# controller.net
KiCad netlist of a schematic drawn in Altium Designer
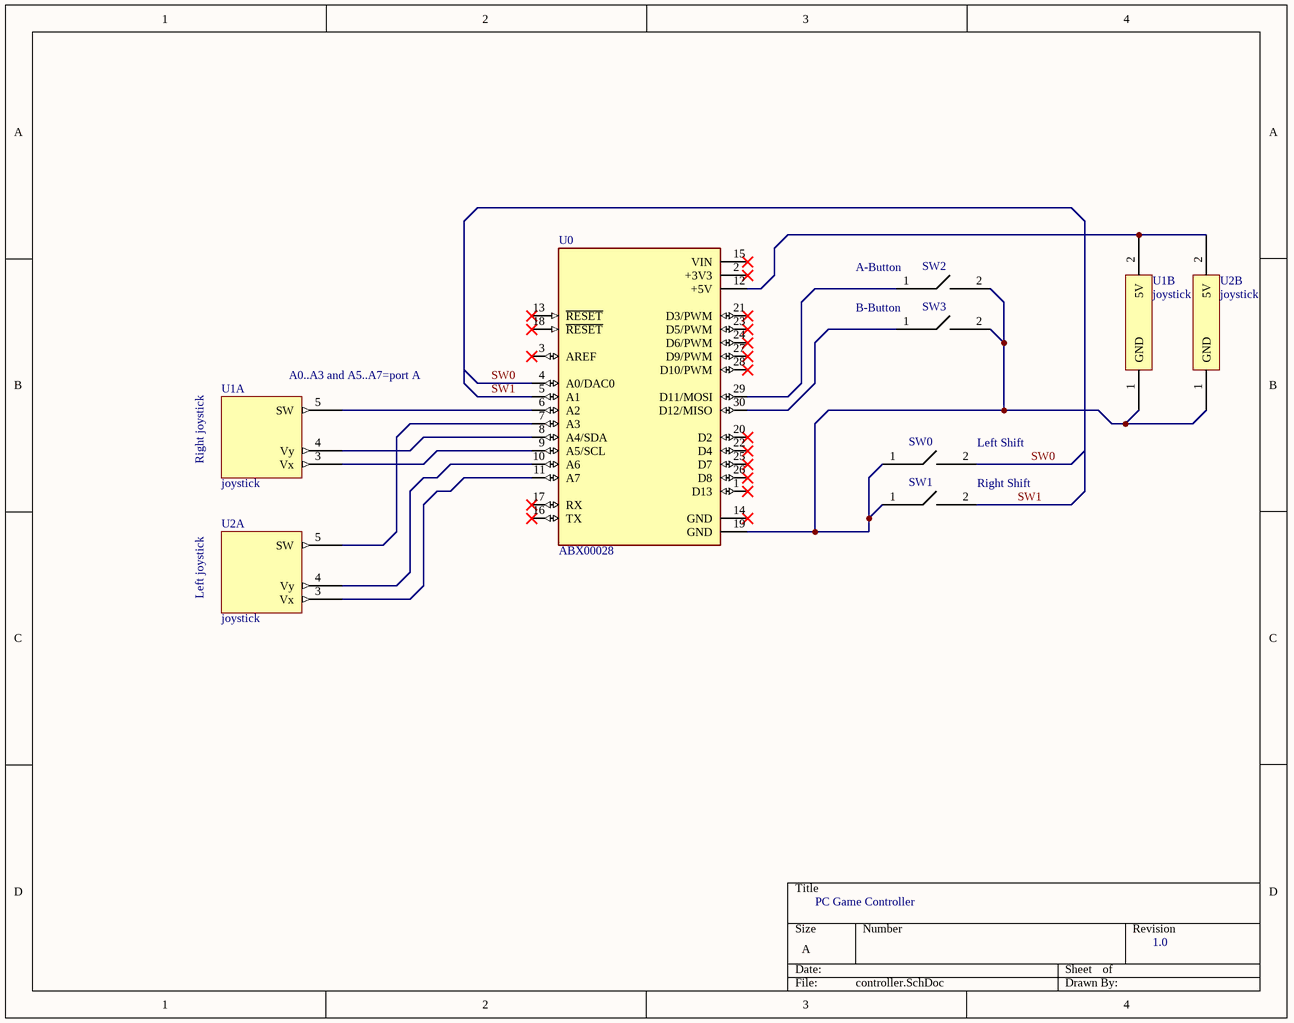
[diagram p0: controller.SchDoc]

(export (version "E")
  (design (tool "Eeschema 10.0.6"))
  (components
    (comp (ref "SW0") (value "~") (footprint "temp switch") (libsource (lib "button") (part "button")))
    (comp (ref "SW1") (value "~") (footprint "temp switch") (libsource (lib "button") (part "button")))
    (comp (ref "SW2") (value "~") (footprint "temp switch") (libsource (lib "button") (part "button")))
    (comp (ref "SW3") (value "~") (footprint "temp switch") (libsource (lib "button") (part "button")))
    (comp (ref "U0")
      (value "ABX00028")
      (footprint "MODULE_ABX00028")
      (description "Arduinoâ€™s 5V compatible board in the smallest available form factor: 45x18mm!")
      (fields (field (name "MP") "Arduino Nano Every") (field (name "MF") "Arduino"))
      (libsource (lib "ABX00028") (part "ABX00028"))
    )
    (comp (ref "U1") (value "joystick") (footprint "joystick") (libsource (lib "") (part "joystick_1")))
    (comp (ref "U2") (value "joystick") (footprint "joystick") (libsource (lib "") (part "joystick_1")))
  )
  (nets
    (net (code "1") (name "/SW0") (class "Default")
      (node (ref "SW0") (pin "2") (pintype "passive"))
      (node (ref "U0") (pin "4") (pinfunction "A0/DAC0_4") (pintype "bidirectional"))
    )
    (net (code "2") (name "/SW1") (class "Default")
      (node (ref "SW1") (pin "2") (pintype "passive"))
      (node (ref "U0") (pin "5") (pinfunction "A1_5") (pintype "bidirectional"))
    )
    (net (code "3") (name "Net-(U0-+5V)") (class "Default")
      (node (ref "U0") (pin "12") (pinfunction "+5V_12") (pintype "power_in"))
      (node (ref "U1") (pin "2") (pinfunction "5V_2") (pintype "power_in"))
      (node (ref "U2") (pin "2") (pinfunction "5V_2") (pintype "power_in"))
    )
    (net (code "4") (name "Net-(U0-A2)") (class "Default")
      (node (ref "U0") (pin "6") (pinfunction "A2_6") (pintype "bidirectional"))
      (node (ref "U1") (pin "5") (pinfunction "SW_5") (pintype "output"))
    )
    (net (code "5") (name "Net-(U0-A3)") (class "Default")
      (node (ref "U0") (pin "7") (pinfunction "A3_7") (pintype "bidirectional"))
      (node (ref "U2") (pin "5") (pinfunction "SW_5") (pintype "output"))
    )
    (net (code "6") (name "Net-(U0-A4{slash}SDA)") (class "Default")
      (node (ref "U0") (pin "8") (pinfunction "A4/SDA_8") (pintype "bidirectional"))
      (node (ref "U1") (pin "4") (pinfunction "Vy_4") (pintype "output"))
    )
    (net (code "7") (name "Net-(U0-A5{slash}SCL)") (class "Default")
      (node (ref "U0") (pin "9") (pinfunction "A5/SCL_9") (pintype "bidirectional"))
      (node (ref "U1") (pin "3") (pinfunction "Vx_3") (pintype "output"))
    )
    (net (code "8") (name "Net-(U0-A6)") (class "Default")
      (node (ref "U0") (pin "10") (pinfunction "A6_10") (pintype "bidirectional"))
      (node (ref "U2") (pin "4") (pinfunction "Vy_4") (pintype "output"))
    )
    (net (code "9") (name "Net-(U0-A7)") (class "Default")
      (node (ref "U0") (pin "11") (pinfunction "A7_11") (pintype "bidirectional"))
      (node (ref "U2") (pin "3") (pinfunction "Vx_3") (pintype "output"))
    )
    (net (code "10") (name "Net-(U0-D11{slash}MOSI)") (class "Default")
      (node (ref "SW2") (pin "1") (pintype "passive"))
      (node (ref "U0") (pin "29") (pinfunction "D11/MOSI_29") (pintype "bidirectional"))
    )
    (net (code "11") (name "Net-(U0-D12{slash}MISO)") (class "Default")
      (node (ref "SW3") (pin "1") (pintype "passive"))
      (node (ref "U0") (pin "30") (pinfunction "D12/MISO_30") (pintype "bidirectional"))
    )
    (net (code "12") (name "Net-(U1B-GND)") (class "Default")
      (node (ref "SW0") (pin "1") (pintype "passive"))
      (node (ref "SW1") (pin "1") (pintype "passive"))
      (node (ref "SW2") (pin "2") (pintype "passive"))
      (node (ref "SW3") (pin "2") (pintype "passive"))
      (node (ref "U0") (pin "19") (pinfunction "GND_19") (pintype "power_in"))
      (node (ref "U1") (pin "1") (pinfunction "GND_1") (pintype "power_in"))
      (node (ref "U2") (pin "1") (pinfunction "GND_1") (pintype "power_in"))
    )
    (net (code "13") (name "unconnected-(U0-+3V3-Pad2)") (class "Default")
      (node (ref "U0") (pin "2") (pinfunction "+3V3_2") (pintype "power_in+no_connect"))
    )
    (net (code "14") (name "unconnected-(U0-AREF-Pad3)") (class "Default")
      (node (ref "U0") (pin "3") (pinfunction "AREF_3") (pintype "bidirectional+no_connect"))
    )
    (net (code "15") (name "unconnected-(U0-D2-Pad20)") (class "Default")
      (node (ref "U0") (pin "20") (pinfunction "D2_20") (pintype "bidirectional+no_connect"))
    )
    (net (code "16") (name "unconnected-(U0-D3{slash}PWM-Pad21)") (class "Default")
      (node (ref "U0") (pin "21") (pinfunction "D3/PWM_21") (pintype "bidirectional+no_connect"))
    )
    (net (code "17") (name "unconnected-(U0-D4-Pad22)") (class "Default")
      (node (ref "U0") (pin "22") (pinfunction "D4_22") (pintype "bidirectional+no_connect"))
    )
    (net (code "18") (name "unconnected-(U0-D5{slash}PWM-Pad23)") (class "Default")
      (node (ref "U0") (pin "23") (pinfunction "D5/PWM_23") (pintype "bidirectional+no_connect"))
    )
    (net (code "19") (name "unconnected-(U0-D6{slash}PWM-Pad24)") (class "Default")
      (node (ref "U0") (pin "24") (pinfunction "D6/PWM_24") (pintype "bidirectional+no_connect"))
    )
    (net (code "20") (name "unconnected-(U0-D7-Pad25)") (class "Default")
      (node (ref "U0") (pin "25") (pinfunction "D7_25") (pintype "bidirectional+no_connect"))
    )
    (net (code "21") (name "unconnected-(U0-D8-Pad26)") (class "Default")
      (node (ref "U0") (pin "26") (pinfunction "D8_26") (pintype "bidirectional+no_connect"))
    )
    (net (code "22") (name "unconnected-(U0-D9{slash}PWM-Pad27)") (class "Default")
      (node (ref "U0") (pin "27") (pinfunction "D9/PWM_27") (pintype "bidirectional+no_connect"))
    )
    (net (code "23") (name "unconnected-(U0-D10{slash}PWM-Pad28)") (class "Default")
      (node (ref "U0") (pin "28") (pinfunction "D10/PWM_28") (pintype "bidirectional+no_connect"))
    )
    (net (code "24") (name "unconnected-(U0-D13-Pad1)") (class "Default")
      (node (ref "U0") (pin "1") (pinfunction "D13_1") (pintype "bidirectional+no_connect"))
    )
    (net (code "25") (name "unconnected-(U0-GND-Pad14)") (class "Default")
      (node (ref "U0") (pin "14") (pinfunction "GND_14") (pintype "power_in+no_connect"))
    )
    (net (code "26") (name "unconnected-(U0-RX-Pad17)") (class "Default")
      (node (ref "U0") (pin "17") (pinfunction "RX_17") (pintype "bidirectional+no_connect"))
    )
    (net (code "27") (name "unconnected-(U0-TX-Pad16)") (class "Default")
      (node (ref "U0") (pin "16") (pinfunction "TX_16") (pintype "bidirectional+no_connect"))
    )
    (net (code "28") (name "unconnected-(U0-VIN-Pad15)") (class "Default")
      (node (ref "U0") (pin "15") (pinfunction "VIN_15") (pintype "power_in+no_connect"))
    )
    (net (code "29") (name "unconnected-(U0-~{RESET}-Pad13)") (class "Default")
      (node (ref "U0") (pin "13") (pinfunction "~{RESET}_13") (pintype "input+no_connect"))
    )
    (net (code "30") (name "unconnected-(U0-~{RESET}-Pad18)") (class "Default")
      (node (ref "U0") (pin "18") (pinfunction "~{RESET}_18") (pintype "input+no_connect"))
    )
  )
)
